# door.net
KiCad netlist of a schematic drawn in EAGLE
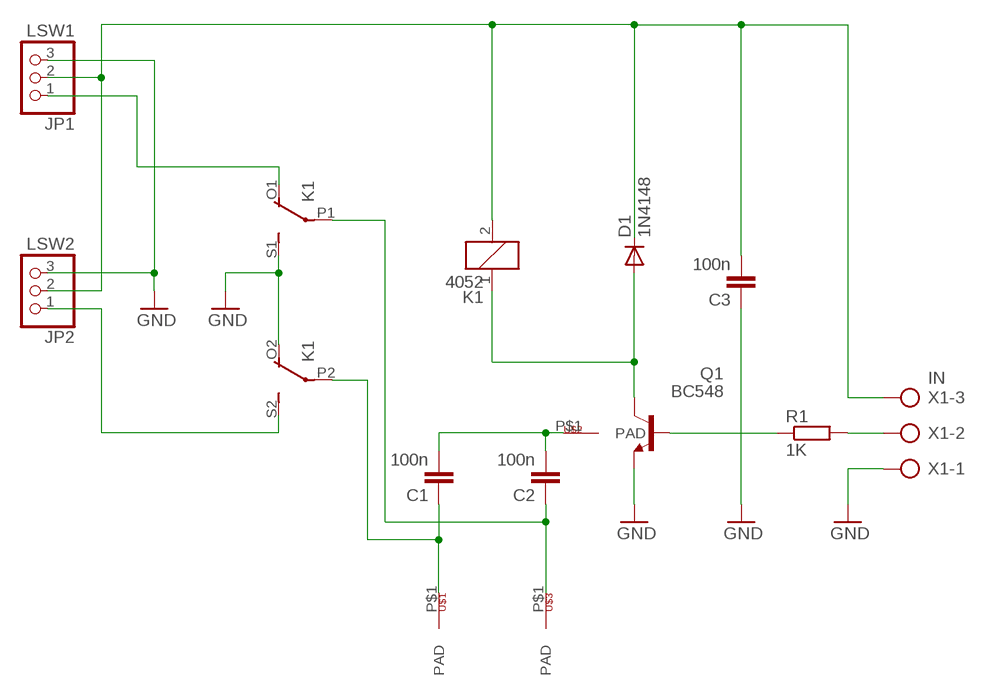
[diagram p0: schematic, sheet 1]

(export (version "E")
  (design (tool "Eeschema 10.0.6"))
  (components
    (comp (ref "C1")
      (value "100n")
      (footprint "eagle-import:C050-025X075")
      (libsource (lib "eagle-import") (part "C-EU050-025X075"))
    )
    (comp (ref "C2")
      (value "100n")
      (footprint "eagle-import:C050-025X075")
      (libsource (lib "eagle-import") (part "C-EU050-025X075"))
    )
    (comp (ref "C3")
      (value "100n")
      (footprint "eagle-import:C050-025X075")
      (libsource (lib "eagle-import") (part "C-EU050-025X075"))
    )
    (comp (ref "D1")
      (value "1N4148")
      (footprint "eagle-import:DO35-7")
      (libsource (lib "eagle-import") (part "1N4148DO35-7"))
    )
    (comp (ref "JP1")
      (value "LSW1")
      (footprint "eagle-import:1X03")
      (libsource (lib "eagle-import") (part "PINHD-1X3"))
    )
    (comp (ref "JP2")
      (value "LSW2")
      (footprint "eagle-import:1X03")
      (libsource (lib "eagle-import") (part "PINHD-1X3"))
    )
    (comp (ref "K1")
      (value "4052")
      (footprint "eagle-import:F4052")
      (libsource (lib "eagle-import") (part "4052"))
    )
    (comp (ref "Q1")
      (value "BC548")
      (footprint "eagle-import:TO92-EBC")
      (libsource (lib "eagle-import") (part "BC548"))
    )
    (comp (ref "R1")
      (value "1K")
      (footprint "eagle-import:0204_7")
      (libsource (lib "eagle-import") (part "R-EU_0204/7"))
    )
    (comp (ref "U$1")
      (value "PAD")
      (footprint "eagle-import:PAD")
      (libsource (lib "eagle-import") (part "PAD"))
    )
    (comp (ref "U$2")
      (value "PAD")
      (footprint "eagle-import:PAD")
      (libsource (lib "eagle-import") (part "PAD"))
    )
    (comp (ref "U$3")
      (value "PAD")
      (footprint "eagle-import:PAD")
      (libsource (lib "eagle-import") (part "PAD"))
    )
    (comp (ref "X1")
      (value "IN")
      (footprint "eagle-import:AK300_3")
      (libsource (lib "eagle-import") (part "AK300/3"))
    )
  )
  (nets
    (net (code "1") (name "GND") (class "Default")
      (node (ref "C3") (pin "1") (pinfunction "1_1") (pintype "passive"))
      (node (ref "JP1") (pin "3") (pinfunction "3_3") (pintype "passive"))
      (node (ref "JP2") (pin "3") (pinfunction "3_3") (pintype "passive"))
      (node (ref "K1") (pin "O2") (pinfunction "O_O2") (pintype "passive"))
      (node (ref "K1") (pin "S1") (pinfunction "S_S1") (pintype "passive"))
      (node (ref "Q1") (pin "E") (pinfunction "E_E") (pintype "passive"))
      (node (ref "X1") (pin "1") (pinfunction "KL_1") (pintype "passive"))
    )
    (net (code "2") (name "Net-(D1-PadA)") (class "Default")
      (node (ref "D1") (pin "A") (pinfunction "A_A") (pintype "passive"))
      (node (ref "K1") (pin "1") (pinfunction "1_1") (pintype "passive"))
      (node (ref "Q1") (pin "C") (pinfunction "C_C") (pintype "passive"))
    )
    (net (code "3") (name "Net-(K1B-O)") (class "Default")
      (node (ref "JP1") (pin "1") (pinfunction "1_1") (pintype "passive"))
      (node (ref "K1") (pin "O1") (pinfunction "O_O1") (pintype "passive"))
    )
    (net (code "4") (name "Net-(K1B-P)") (class "Default")
      (node (ref "C2") (pin "1") (pinfunction "1_1") (pintype "passive"))
      (node (ref "K1") (pin "P1") (pinfunction "P_P1") (pintype "passive"))
      (node (ref "U$3") (pin "P$1") (pinfunction "PAD_P$1") (pintype "bidirectional"))
    )
    (net (code "5") (name "Net-(K1C-P)") (class "Default")
      (node (ref "C1") (pin "1") (pinfunction "1_1") (pintype "passive"))
      (node (ref "K1") (pin "P2") (pinfunction "P_P2") (pintype "passive"))
      (node (ref "U$1") (pin "P$1") (pinfunction "PAD_P$1") (pintype "bidirectional"))
    )
    (net (code "6") (name "Net-(K1C-S)") (class "Default")
      (node (ref "JP2") (pin "1") (pinfunction "1_1") (pintype "passive"))
      (node (ref "K1") (pin "S2") (pinfunction "S_S2") (pintype "passive"))
    )
    (net (code "7") (name "Net-(Q1-PadB)") (class "Default")
      (node (ref "Q1") (pin "B") (pinfunction "B_B") (pintype "passive"))
      (node (ref "R1") (pin "1") (pinfunction "1_1") (pintype "passive"))
    )
    (net (code "8") (name "Net-(U$2-PAD)") (class "Default")
      (node (ref "C1") (pin "2") (pinfunction "2_2") (pintype "passive"))
      (node (ref "C2") (pin "2") (pinfunction "2_2") (pintype "passive"))
      (node (ref "U$2") (pin "P$1") (pinfunction "PAD_P$1") (pintype "bidirectional"))
    )
    (net (code "9") (name "Net-(X1B-KL)") (class "Default")
      (node (ref "R1") (pin "2") (pinfunction "2_2") (pintype "passive"))
      (node (ref "X1") (pin "2") (pinfunction "KL_2") (pintype "passive"))
    )
    (net (code "10") (name "Net-(X1C-KL)") (class "Default")
      (node (ref "C3") (pin "2") (pinfunction "2_2") (pintype "passive"))
      (node (ref "D1") (pin "C") (pinfunction "C_C") (pintype "passive"))
      (node (ref "JP1") (pin "2") (pinfunction "2_2") (pintype "passive"))
      (node (ref "JP2") (pin "2") (pinfunction "2_2") (pintype "passive"))
      (node (ref "K1") (pin "2") (pinfunction "2_2") (pintype "passive"))
      (node (ref "X1") (pin "3") (pinfunction "KL_3") (pintype "passive"))
    )
  )
)
